# brain2_v02.net
KiCad netlist of a schematic drawn in EAGLE
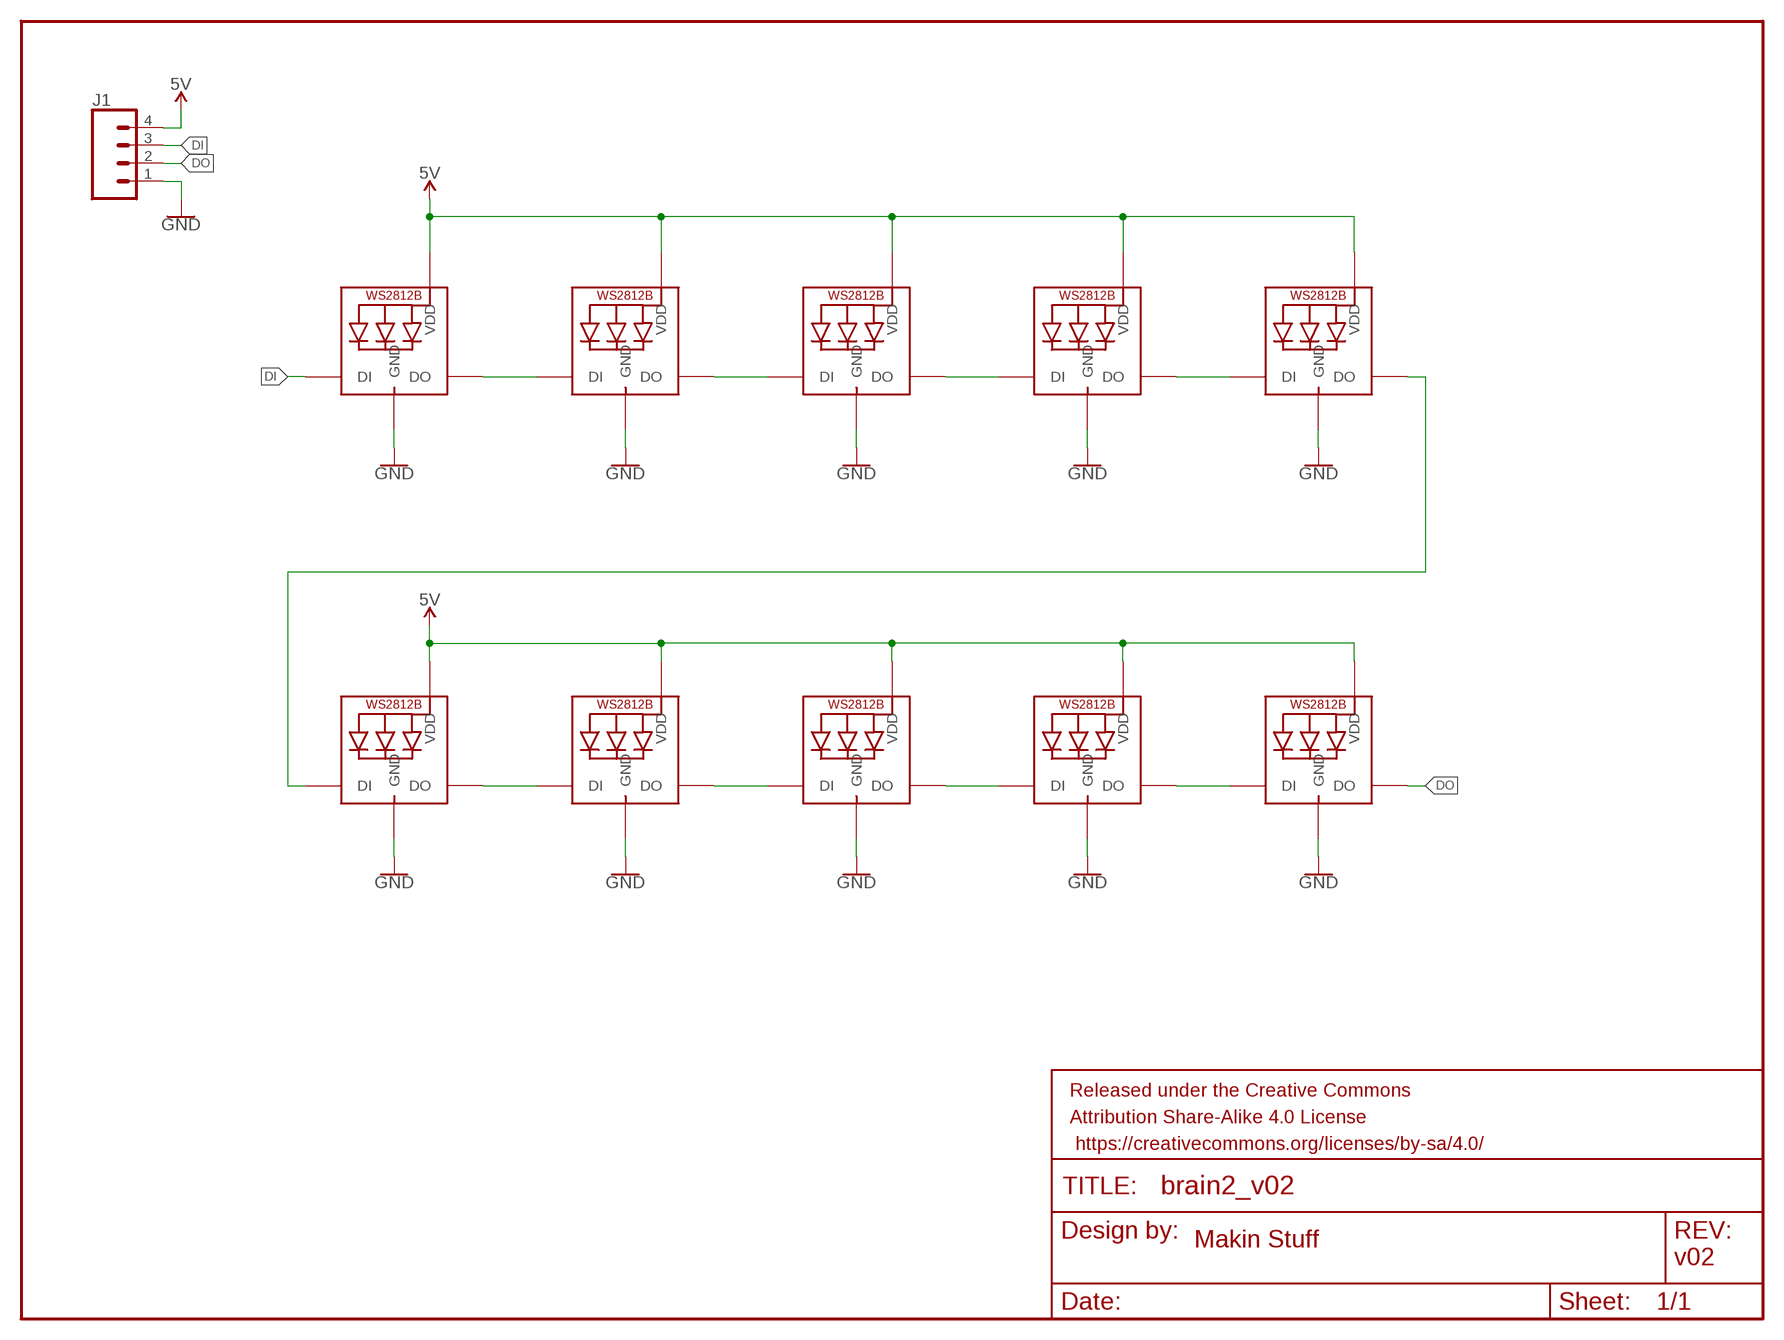
[diagram p0: schematic, sheet 1]

(export (version "E")
  (design (tool "Eeschema 10.0.6"))
  (components
    (comp (ref "FRAME1")
      (value "FRAME-LETTER")
      (footprint "eagle-import:CREATIVE_COMMONS")
      (libsource (lib "eagle-import") (part "FRAME-LETTER"))
    )
    (comp (ref "J1")
      (value "CONN_04PTH")
      (footprint "eagle-import:1X04")
      (libsource (lib "eagle-import") (part "CONN_04PTH"))
    )
    (comp (ref "LED1")
      (value "3.5X3.5_RGB_LED3.5X3.5")
      (footprint "eagle-import:3.5X3.5_RGB_LED")
      (libsource (lib "eagle-import") (part "3.5X3.5_RGB_LED3.5X3.5"))
    )
    (comp (ref "LED2")
      (value "3.5X3.5_RGB_LED3.5X3.5")
      (footprint "eagle-import:3.5X3.5_RGB_LED")
      (libsource (lib "eagle-import") (part "3.5X3.5_RGB_LED3.5X3.5"))
    )
    (comp (ref "LED3")
      (value "3.5X3.5_RGB_LED3.5X3.5")
      (footprint "eagle-import:3.5X3.5_RGB_LED")
      (libsource (lib "eagle-import") (part "3.5X3.5_RGB_LED3.5X3.5"))
    )
    (comp (ref "LED4")
      (value "3.5X3.5_RGB_LED3.5X3.5")
      (footprint "eagle-import:3.5X3.5_RGB_LED")
      (libsource (lib "eagle-import") (part "3.5X3.5_RGB_LED3.5X3.5"))
    )
    (comp (ref "LED5")
      (value "3.5X3.5_RGB_LED3.5X3.5")
      (footprint "eagle-import:3.5X3.5_RGB_LED")
      (libsource (lib "eagle-import") (part "3.5X3.5_RGB_LED3.5X3.5"))
    )
    (comp (ref "LED6")
      (value "3.5X3.5_RGB_LED3.5X3.5")
      (footprint "eagle-import:3.5X3.5_RGB_LED")
      (libsource (lib "eagle-import") (part "3.5X3.5_RGB_LED3.5X3.5"))
    )
    (comp (ref "LED7")
      (value "3.5X3.5_RGB_LED3.5X3.5")
      (footprint "eagle-import:3.5X3.5_RGB_LED")
      (libsource (lib "eagle-import") (part "3.5X3.5_RGB_LED3.5X3.5"))
    )
    (comp (ref "LED8")
      (value "3.5X3.5_RGB_LED3.5X3.5")
      (footprint "eagle-import:3.5X3.5_RGB_LED")
      (libsource (lib "eagle-import") (part "3.5X3.5_RGB_LED3.5X3.5"))
    )
    (comp (ref "LED9")
      (value "3.5X3.5_RGB_LED3.5X3.5")
      (footprint "eagle-import:3.5X3.5_RGB_LED")
      (libsource (lib "eagle-import") (part "3.5X3.5_RGB_LED3.5X3.5"))
    )
    (comp (ref "LED10")
      (value "3.5X3.5_RGB_LED3.5X3.5")
      (footprint "eagle-import:3.5X3.5_RGB_LED")
      (libsource (lib "eagle-import") (part "3.5X3.5_RGB_LED3.5X3.5"))
    )
  )
  (nets
    (net (code "1") (name "5V") (class "Default")
      (node (ref "J1") (pin "4") (pinfunction "4_4") (pintype "passive"))
      (node (ref "LED1") (pin "4") (pinfunction "VDD_4") (pintype "power_in"))
      (node (ref "LED10") (pin "4") (pinfunction "VDD_4") (pintype "power_in"))
      (node (ref "LED2") (pin "4") (pinfunction "VDD_4") (pintype "power_in"))
      (node (ref "LED3") (pin "4") (pinfunction "VDD_4") (pintype "power_in"))
      (node (ref "LED4") (pin "4") (pinfunction "VDD_4") (pintype "power_in"))
      (node (ref "LED5") (pin "4") (pinfunction "VDD_4") (pintype "power_in"))
      (node (ref "LED6") (pin "4") (pinfunction "VDD_4") (pintype "power_in"))
      (node (ref "LED7") (pin "4") (pinfunction "VDD_4") (pintype "power_in"))
      (node (ref "LED8") (pin "4") (pinfunction "VDD_4") (pintype "power_in"))
      (node (ref "LED9") (pin "4") (pinfunction "VDD_4") (pintype "power_in"))
    )
    (net (code "2") (name "DI") (class "Default")
      (node (ref "J1") (pin "3") (pinfunction "3_3") (pintype "passive"))
      (node (ref "LED1") (pin "3") (pinfunction "DI_3") (pintype "input"))
    )
    (net (code "3") (name "DO") (class "Default")
      (node (ref "J1") (pin "2") (pinfunction "2_2") (pintype "passive"))
      (node (ref "LED10") (pin "1") (pinfunction "DO_1") (pintype "output"))
    )
    (net (code "4") (name "GND") (class "Default")
      (node (ref "J1") (pin "1") (pinfunction "1_1") (pintype "passive"))
      (node (ref "LED1") (pin "2") (pinfunction "GND_2") (pintype "power_in"))
      (node (ref "LED10") (pin "2") (pinfunction "GND_2") (pintype "power_in"))
      (node (ref "LED2") (pin "2") (pinfunction "GND_2") (pintype "power_in"))
      (node (ref "LED3") (pin "2") (pinfunction "GND_2") (pintype "power_in"))
      (node (ref "LED4") (pin "2") (pinfunction "GND_2") (pintype "power_in"))
      (node (ref "LED5") (pin "2") (pinfunction "GND_2") (pintype "power_in"))
      (node (ref "LED6") (pin "2") (pinfunction "GND_2") (pintype "power_in"))
      (node (ref "LED7") (pin "2") (pinfunction "GND_2") (pintype "power_in"))
      (node (ref "LED8") (pin "2") (pinfunction "GND_2") (pintype "power_in"))
      (node (ref "LED9") (pin "2") (pinfunction "GND_2") (pintype "power_in"))
    )
    (net (code "5") (name "Net-(LED1-DO)") (class "Default")
      (node (ref "LED1") (pin "1") (pinfunction "DO_1") (pintype "output"))
      (node (ref "LED2") (pin "3") (pinfunction "DI_3") (pintype "input"))
    )
    (net (code "6") (name "Net-(LED2-DO)") (class "Default")
      (node (ref "LED2") (pin "1") (pinfunction "DO_1") (pintype "output"))
      (node (ref "LED3") (pin "3") (pinfunction "DI_3") (pintype "input"))
    )
    (net (code "7") (name "Net-(LED3-DO)") (class "Default")
      (node (ref "LED3") (pin "1") (pinfunction "DO_1") (pintype "output"))
      (node (ref "LED4") (pin "3") (pinfunction "DI_3") (pintype "input"))
    )
    (net (code "8") (name "Net-(LED4-DO)") (class "Default")
      (node (ref "LED4") (pin "1") (pinfunction "DO_1") (pintype "output"))
      (node (ref "LED5") (pin "3") (pinfunction "DI_3") (pintype "input"))
    )
    (net (code "9") (name "Net-(LED5-DO)") (class "Default")
      (node (ref "LED5") (pin "1") (pinfunction "DO_1") (pintype "output"))
      (node (ref "LED6") (pin "3") (pinfunction "DI_3") (pintype "input"))
    )
    (net (code "10") (name "Net-(LED6-DO)") (class "Default")
      (node (ref "LED6") (pin "1") (pinfunction "DO_1") (pintype "output"))
      (node (ref "LED7") (pin "3") (pinfunction "DI_3") (pintype "input"))
    )
    (net (code "11") (name "Net-(LED7-DO)") (class "Default")
      (node (ref "LED7") (pin "1") (pinfunction "DO_1") (pintype "output"))
      (node (ref "LED8") (pin "3") (pinfunction "DI_3") (pintype "input"))
    )
    (net (code "12") (name "Net-(LED8-DO)") (class "Default")
      (node (ref "LED8") (pin "1") (pinfunction "DO_1") (pintype "output"))
      (node (ref "LED9") (pin "3") (pinfunction "DI_3") (pintype "input"))
    )
    (net (code "13") (name "Net-(LED10-DI)") (class "Default")
      (node (ref "LED10") (pin "3") (pinfunction "DI_3") (pintype "input"))
      (node (ref "LED9") (pin "1") (pinfunction "DO_1") (pintype "output"))
    )
  )
)
